# Flexi_encoder_BOB.net
KiCad netlist of a schematic drawn in Altium Designer
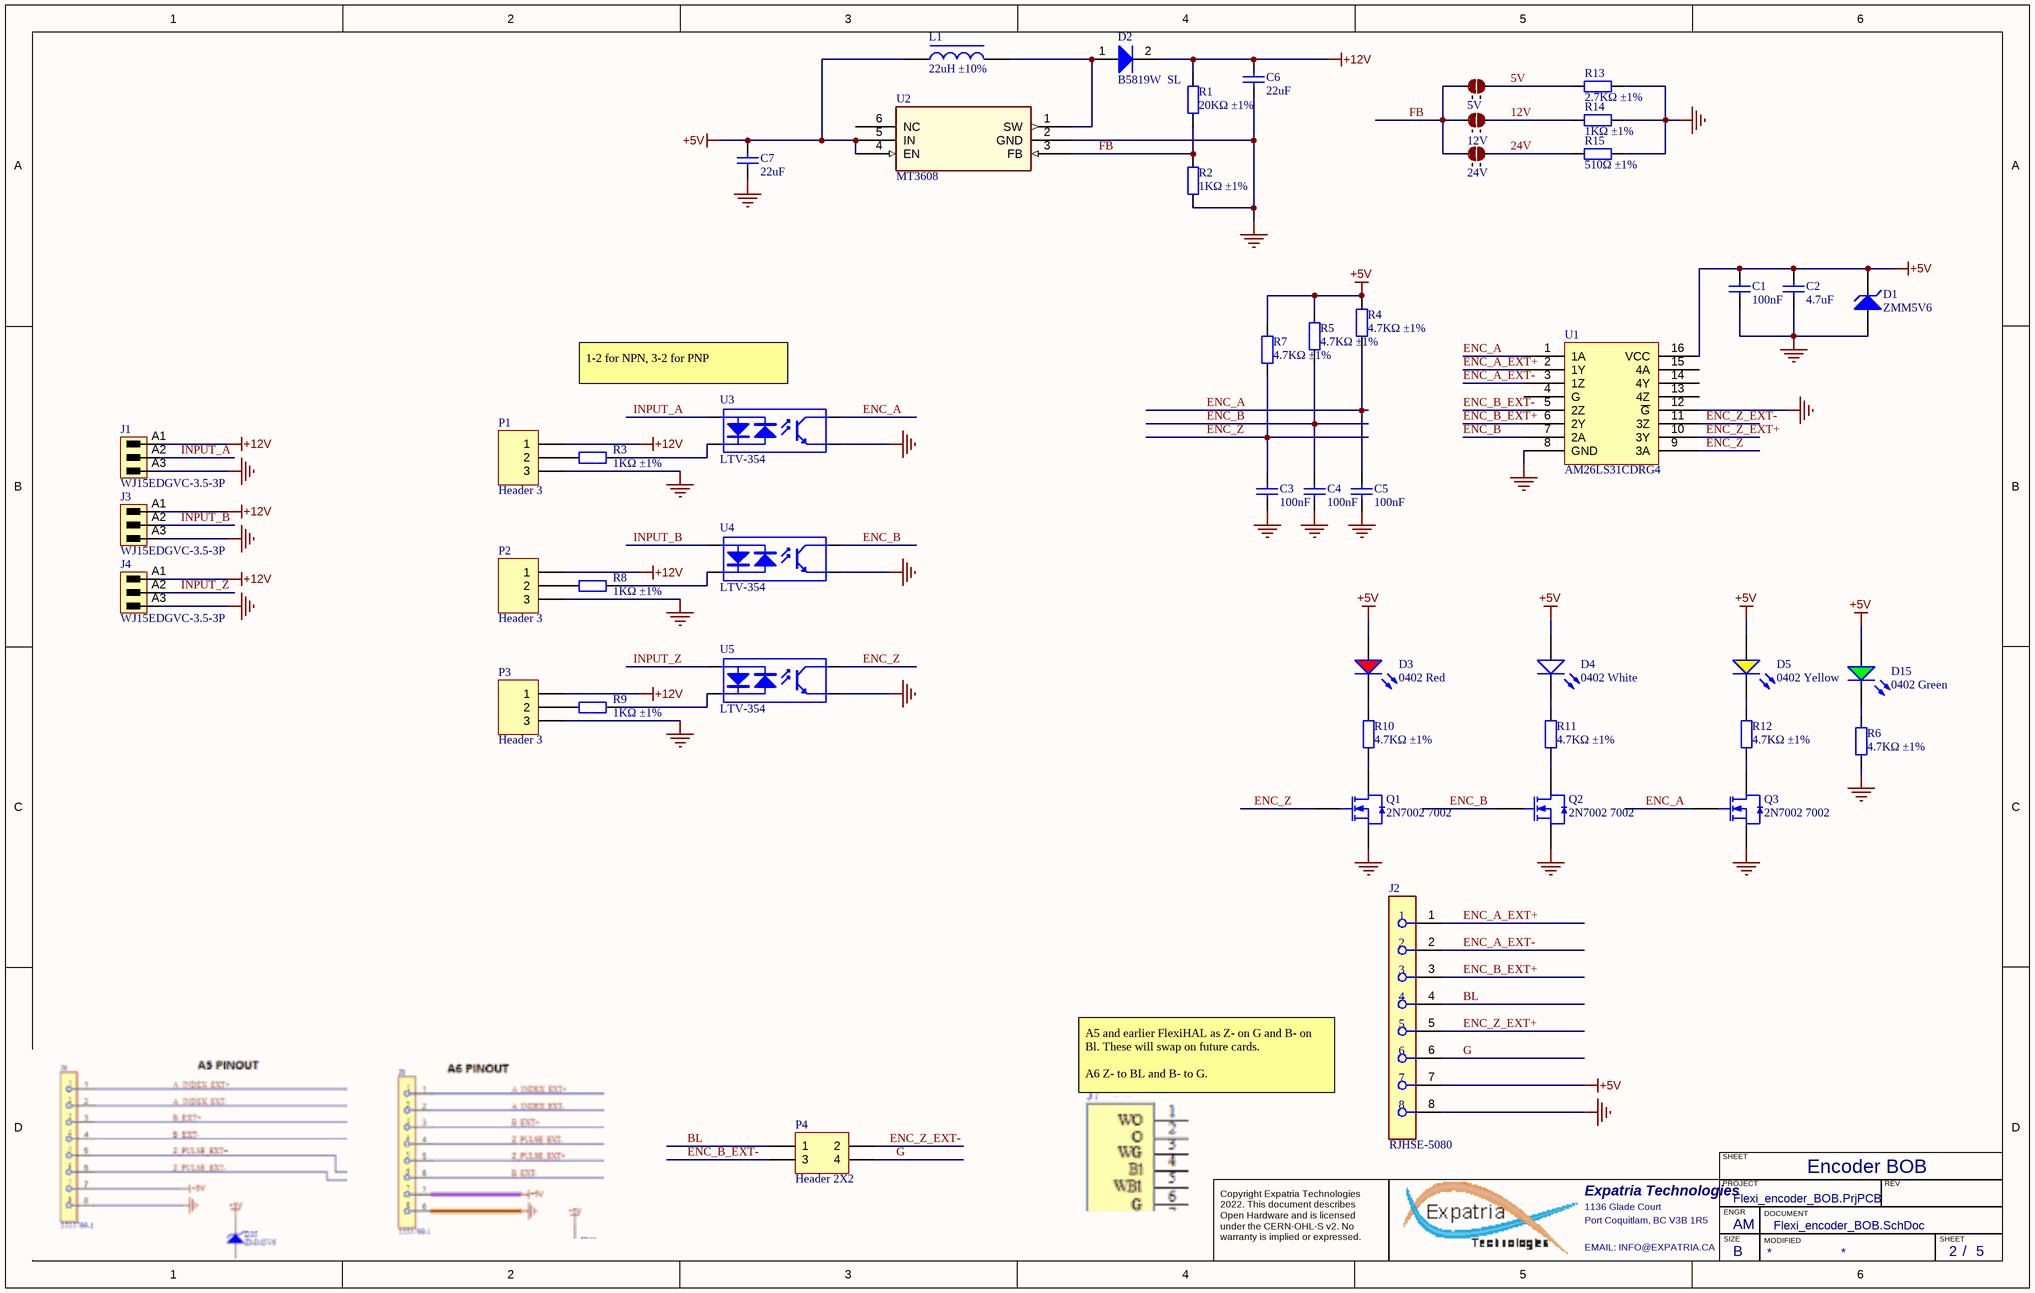
[diagram p0: Flexi_encoder_BOB.SchDoc]

(export (version "E")
  (design (tool "Eeschema 10.0.6"))
  (components
    (comp (ref "5V")
      (value "2 way net solder junction - Normally Open")
      (footprint "2waySolder_NO")
      (libsource (lib "NetTie") (part "2waySolderNO"))
    )
    (comp (ref "12V")
      (value "2 way net solder junction - Normally Open")
      (footprint "2waySolder_NO")
      (libsource (lib "NetTie") (part "2waySolderNO"))
    )
    (comp (ref "24V")
      (value "2 way net solder junction - Normally Open")
      (footprint "2waySolder_NO")
      (libsource (lib "NetTie") (part "2waySolderNO"))
    )
    (comp (ref "C1")
      (value "100nF")
      (footprint "0402_C")
      (description "Chip capacitors")
      (fields
        (field (name "MANUFACTURER") "Samsung Electro-Mechanics")
        (field (name "PARTNUMBER") "CL05B104KO5NNNC")
      )
      (libsource (lib "Cap") (part "0402 100nF (104) 10% 16V"))
    )
    (comp (ref "C2")
      (value "4.7uF")
      (footprint "0402_C")
      (description "Chip capacitor")
      (fields
        (field (name "MANUFACTURER") "Samsung Electro-Mechanics")
        (field (name "PARTNUMBER") "CL05A475MP5NRNC")
      )
      (libsource (lib "Cap") (part "0402 4.7uF (475) 20% 10V"))
    )
    (comp (ref "C3")
      (value "100nF")
      (footprint "0402_C")
      (description "Chip capacitors")
      (fields
        (field (name "MANUFACTURER") "Samsung Electro-Mechanics")
        (field (name "PARTNUMBER") "CL05B104KO5NNNC")
      )
      (libsource (lib "Cap") (part "0402 100nF (104) 10% 16V"))
    )
    (comp (ref "C4")
      (value "100nF")
      (footprint "0402_C")
      (description "Chip capacitors")
      (fields
        (field (name "MANUFACTURER") "Samsung Electro-Mechanics")
        (field (name "PARTNUMBER") "CL05B104KO5NNNC")
      )
      (libsource (lib "Cap") (part "0402 100nF (104) 10% 16V"))
    )
    (comp (ref "C5")
      (value "100nF")
      (footprint "0402_C")
      (description "Chip capacitors")
      (fields
        (field (name "MANUFACTURER") "Samsung Electro-Mechanics")
        (field (name "PARTNUMBER") "CL05B104KO5NNNC")
      )
      (libsource (lib "Cap") (part "0402 100nF (104) 10% 16V"))
    )
    (comp (ref "C6")
      (value "22uF")
      (footprint "0805_C")
      (description "Chip capacitors")
      (fields
        (field (name "MANUFACTURER") "Samsung Electro-Mechanics")
        (field (name "PARTNUMBER") "CL21A226MAQNNNE")
      )
      (libsource (lib "Cap") (part "0805 22uF (226) 20% 25V"))
    )
    (comp (ref "C7")
      (value "22uF")
      (footprint "0805_C")
      (description "Chip capacitors")
      (fields
        (field (name "MANUFACTURER") "Samsung Electro-Mechanics")
        (field (name "PARTNUMBER") "CL21A226MAQNNNE")
      )
      (libsource (lib "Cap") (part "0805 22uF (226) 20% 25V"))
    )
    (comp (ref "D1")
      (value "ZMM5V6")
      (footprint "LL-34")
      (description "500mW - 0.1uA @ 1V 5.6V LL-34 Zener Diodes ROHS")
      (libsource (lib "Zener") (part "LL-34 ZMM5V6"))
    )
    (comp (ref "D2")
      (value "B5819W  SL")
      (footprint "SOD-123")
      (description "Schottky Diode")
      (libsource (lib "Diode") (part "SOD-123 B5819W  SL"))
    )
    (comp (ref "D3")
      (value "0402 Red")
      (footprint "LED 0402_1005 RED")
      (description "LED")
      (libsource (lib "LED") (part "0402 LED Red"))
    )
    (comp (ref "D4")
      (value "0402 White")
      (footprint "LED 0402_1005 RED")
      (description "LED")
      (libsource (lib "LED") (part "0402 LED White"))
    )
    (comp (ref "D5")
      (value "0402 Yellow")
      (footprint "LED 0402_1005 RED")
      (description "LED")
      (libsource (lib "LED") (part "0402 LED Yellow"))
    )
    (comp (ref "D15")
      (value "0402 Green")
      (footprint "LED 0402_1005 RED")
      (description "LED")
      (libsource (lib "LED") (part "0402 LED Green"))
    )
    (comp (ref "J1")
      (value "WJ15EDGVC-3.5-3P")
      (footprint "691321100003 - 3.5mm  3p")
      (fields (field (name "MANUFACTURER") "Ningbo Kangnex Elec"))
      (libsource (lib "Universal_CNC_Breakout") (part "3.5mm Terminal Header 3p"))
    )
    (comp (ref "J2")
      (value "RJHSE-5080")
      (footprint "FP-RJHSE-5080-MFG")
      (description "CONN MOD JACK 8P8C R/A UNSHLD")
      (fields
        (field (name "MANUFACTURER PART NUMBER") "E5J88-00LJG2-L")
        (field (name "MANUFACTURER") "Pulse Electronics Network")
      )
      (libsource (lib "Altium Content Vault") (part "b0a0b555dd3abf3683e7c330df25cc4"))
    )
    (comp (ref "J3")
      (value "WJ15EDGVC-3.5-3P")
      (footprint "691321100003 - 3.5mm  3p")
      (fields (field (name "MANUFACTURER") "Ningbo Kangnex Elec"))
      (libsource (lib "Universal_CNC_Breakout") (part "3.5mm Terminal Header 3p"))
    )
    (comp (ref "J4")
      (value "WJ15EDGVC-3.5-3P")
      (footprint "691321100003 - 3.5mm  3p")
      (fields (field (name "MANUFACTURER") "Ningbo Kangnex Elec"))
      (libsource (lib "Universal_CNC_Breakout") (part "3.5mm Terminal Header 3p"))
    )
    (comp (ref "L1")
      (value "22uH ±10%")
      (footprint "INDP4040X30N")
      (description "1A 22uH ±20% SMD,4x4x3mm Power Inductors ROHS")
      (libsource (lib "IUD") (part "4x4x3 22uH 20%"))
    )
    (comp (ref "P1")
      (value "Header 3")
      (footprint "Miscellaneous Connectors:HDR1X3")
      (description "Header, 3-Pin")
      (fields (field (name "PUBLISHER") "Altium Limited"))
      (libsource (lib "Miscellaneous Connectors") (part "Header 3"))
    )
    (comp (ref "P2")
      (value "Header 3")
      (footprint "Miscellaneous Connectors:HDR1X3")
      (description "Header, 3-Pin")
      (fields (field (name "PUBLISHER") "Altium Limited"))
      (libsource (lib "Miscellaneous Connectors") (part "Header 3"))
    )
    (comp (ref "P3")
      (value "Header 3")
      (footprint "Miscellaneous Connectors:HDR1X3")
      (description "Header, 3-Pin")
      (fields (field (name "PUBLISHER") "Altium Limited"))
      (libsource (lib "Miscellaneous Connectors") (part "Header 3"))
    )
    (comp (ref "P4")
      (value "Header 2X2")
      (footprint "Miscellaneous Connectors:HDR2X2")
      (description "Header, 2-Pin, Dual row")
      (libsource (lib "Miscellaneous Connectors") (part "Header 2X2"))
    )
    (comp (ref "Q1")
      (value "2N7002 7002")
      (footprint "SOT-23(SOT-23-3)")
      (description "MOS(场效应管)")
      (libsource (lib "MOS") (part "2N7002 7002"))
    )
    (comp (ref "Q2")
      (value "2N7002 7002")
      (footprint "SOT-23(SOT-23-3)")
      (description "MOS(场效应管)")
      (libsource (lib "MOS") (part "2N7002 7002"))
    )
    (comp (ref "Q3")
      (value "2N7002 7002")
      (footprint "SOT-23(SOT-23-3)")
      (description "MOS(场效应管)")
      (libsource (lib "MOS") (part "2N7002 7002"))
    )
    (comp (ref "R1")
      (value "20KΩ ±1%")
      (footprint "0402_R")
      (description "Chip resistor")
      (fields (field (name "MANUFACTURER") "Uniroyal Elec") (field (name "PARTNUMBER") "0402WGF2002TCE"))
      (libsource (lib "RES") (part "0402 20K (2002) 1%"))
    )
    (comp (ref "R2")
      (value "1KΩ ±1%")
      (footprint "0402_R")
      (description "Chip resistor")
      (fields (field (name "MANUFACTURER") "Uniroyal Elec") (field (name "PARTNUMBER") "0402WGF1001TCE"))
      (libsource (lib "") (part "0402 1K (1001) 1%_1"))
    )
    (comp (ref "R3")
      (value "1KΩ ±1%")
      (footprint "0402_R")
      (description "Chip resistor")
      (fields (field (name "MANUFACTURER") "Uniroyal Elec") (field (name "PARTNUMBER") "0402WGF1001TCE"))
      (libsource (lib "RES") (part "0402 1K (1001) 1%"))
    )
    (comp (ref "R4")
      (value "4.7KΩ ±1%")
      (footprint "0402_R")
      (description "Chip resistor")
      (fields (field (name "MANUFACTURER") "Uniroyal Elec") (field (name "PARTNUMBER") "0402WGF4701TCE"))
      (libsource (lib "RES") (part "0402 4.7K (4701) 1%"))
    )
    (comp (ref "R5")
      (value "4.7KΩ ±1%")
      (footprint "0402_R")
      (description "Chip resistor")
      (fields (field (name "MANUFACTURER") "Uniroyal Elec") (field (name "PARTNUMBER") "0402WGF4701TCE"))
      (libsource (lib "RES") (part "0402 4.7K (4701) 1%"))
    )
    (comp (ref "R6")
      (value "4.7KΩ ±1%")
      (footprint "0402_R")
      (description "Chip resistor")
      (fields (field (name "MANUFACTURER") "Uniroyal Elec") (field (name "PARTNUMBER") "0402WGF4701TCE"))
      (libsource (lib "RES") (part "0402 4.7K (4701) 1%"))
    )
    (comp (ref "R7")
      (value "4.7KΩ ±1%")
      (footprint "0402_R")
      (description "Chip resistor")
      (fields (field (name "MANUFACTURER") "Uniroyal Elec") (field (name "PARTNUMBER") "0402WGF4701TCE"))
      (libsource (lib "RES") (part "0402 4.7K (4701) 1%"))
    )
    (comp (ref "R8")
      (value "1KΩ ±1%")
      (footprint "0402_R")
      (description "Chip resistor")
      (fields (field (name "MANUFACTURER") "Uniroyal Elec") (field (name "PARTNUMBER") "0402WGF1001TCE"))
      (libsource (lib "RES") (part "0402 1K (1001) 1%"))
    )
    (comp (ref "R9")
      (value "1KΩ ±1%")
      (footprint "0402_R")
      (description "Chip resistor")
      (fields (field (name "MANUFACTURER") "Uniroyal Elec") (field (name "PARTNUMBER") "0402WGF1001TCE"))
      (libsource (lib "RES") (part "0402 1K (1001) 1%"))
    )
    (comp (ref "R10")
      (value "4.7KΩ ±1%")
      (footprint "0402_R")
      (description "Chip resistor")
      (fields (field (name "MANUFACTURER") "Uniroyal Elec") (field (name "PARTNUMBER") "0402WGF4701TCE"))
      (libsource (lib "RES") (part "0402 4.7K (4701) 1%"))
    )
    (comp (ref "R11")
      (value "4.7KΩ ±1%")
      (footprint "0402_R")
      (description "Chip resistor")
      (fields (field (name "MANUFACTURER") "Uniroyal Elec") (field (name "PARTNUMBER") "0402WGF4701TCE"))
      (libsource (lib "RES") (part "0402 4.7K (4701) 1%"))
    )
    (comp (ref "R12")
      (value "4.7KΩ ±1%")
      (footprint "0402_R")
      (description "Chip resistor")
      (fields (field (name "MANUFACTURER") "Uniroyal Elec") (field (name "PARTNUMBER") "0402WGF4701TCE"))
      (libsource (lib "RES") (part "0402 4.7K (4701) 1%"))
    )
    (comp (ref "R13")
      (value "2.7KΩ ±1%")
      (footprint "0603_R")
      (description "Chip resistor")
      (fields (field (name "MANUFACTURER") "Uniroyal Elec") (field (name "PARTNUMBER") "0603WAF2701T5E"))
      (libsource (lib "RES") (part "0603 2.7K (2701) 1%"))
    )
    (comp (ref "R14")
      (value "1KΩ ±1%")
      (footprint "0402_R")
      (description "Chip resistor")
      (fields (field (name "MANUFACTURER") "Uniroyal Elec") (field (name "PARTNUMBER") "0402WGF1001TCE"))
      (libsource (lib "RES") (part "0402 1K (1001) 1%"))
    )
    (comp (ref "R15")
      (value "510Ω ±1%")
      (footprint "0402_R")
      (description "Chip resistor")
      (fields (field (name "MANUFACTURER") "Uniroyal Elec") (field (name "PARTNUMBER") "0402WGF5100TCE"))
      (libsource (lib "RES") (part "0402 510R (5100) 1%"))
    )
    (comp (ref "U1")
      (value "AM26LS31CDRG4")
      (footprint "SOIC-16_150mil")
      (description "4/0 Driver - RS422, RS485 16-SOIC")
      (libsource (lib "IC") (part "AM26LS31CDRG4_[C6179]"))
    )
    (comp (ref "U2")
      (value "MT3608")
      (footprint "TSOT23-6SOT23-6_AER")
      (description "No Description Available")
      (libsource (lib "Universal_CNC_Breakout") (part "MT3608"))
    )
    (comp (ref "U3")
      (value "LTV-354")
      (footprint "Miscellaneous Devices LC:SOP-4_P2.54")
      (libsource (lib "IC") (part "LTV-354"))
    )
    (comp (ref "U4")
      (value "LTV-354")
      (footprint "Miscellaneous Devices LC:SOP-4_P2.54")
      (libsource (lib "IC") (part "LTV-354"))
    )
    (comp (ref "U5")
      (value "LTV-354")
      (footprint "Miscellaneous Devices LC:SOP-4_P2.54")
      (libsource (lib "IC") (part "LTV-354"))
    )
  )
  (nets
    (net (code "1") (name "+5V") (class "Default")
      (node (ref "C1") (pin "1") (pinfunction "1_1") (pintype "passive"))
      (node (ref "C2") (pin "1") (pinfunction "1_1") (pintype "passive"))
      (node (ref "C7") (pin "2") (pinfunction "2_2") (pintype "passive"))
      (node (ref "D1") (pin "2") (pinfunction "K_2") (pintype "passive"))
      (node (ref "D15") (pin "A") (pinfunction "A_A") (pintype "passive"))
      (node (ref "D3") (pin "A") (pinfunction "A_A") (pintype "passive"))
      (node (ref "D4") (pin "A") (pinfunction "A_A") (pintype "passive"))
      (node (ref "D5") (pin "A") (pinfunction "A_A") (pintype "passive"))
      (node (ref "J2") (pin "7") (pinfunction "7_7") (pintype "passive"))
      (node (ref "L1") (pin "1") (pinfunction "1_1") (pintype "passive"))
      (node (ref "R4") (pin "2") (pinfunction "2_2") (pintype "passive"))
      (node (ref "R5") (pin "2") (pinfunction "2_2") (pintype "passive"))
      (node (ref "R7") (pin "2") (pinfunction "2_2") (pintype "passive"))
      (node (ref "U1") (pin "16") (pinfunction "VCC_16") (pintype "passive"))
      (node (ref "U2") (pin "4") (pinfunction "EN_4") (pintype "input"))
      (node (ref "U2") (pin "5") (pinfunction "IN_5") (pintype "power_in"))
    )
    (net (code "2") (name "+12V") (class "Default")
      (node (ref "C6") (pin "2") (pinfunction "2_2") (pintype "passive"))
      (node (ref "D2") (pin "2") (pinfunction "K_2") (pintype "passive"))
      (node (ref "J1") (pin "A1") (pinfunction "A1_A1") (pintype "passive"))
      (node (ref "J3") (pin "A1") (pinfunction "A1_A1") (pintype "passive"))
      (node (ref "J4") (pin "A1") (pinfunction "A1_A1") (pintype "passive"))
      (node (ref "P1") (pin "1") (pinfunction "1_1") (pintype "passive"))
      (node (ref "P2") (pin "1") (pinfunction "1_1") (pintype "passive"))
      (node (ref "P3") (pin "1") (pinfunction "1_1") (pintype "passive"))
      (node (ref "R1") (pin "2") (pinfunction "2_2") (pintype "passive"))
    )
    (net (code "3") (name "/5V") (class "Default")
      (node (ref "5V") (pin "2") (pinfunction "2_2") (pintype "passive"))
      (node (ref "R13") (pin "1") (pinfunction "1_1") (pintype "passive"))
    )
    (net (code "4") (name "/12V") (class "Default")
      (node (ref "12V") (pin "2") (pinfunction "2_2") (pintype "passive"))
      (node (ref "R14") (pin "2") (pinfunction "2_2") (pintype "passive"))
    )
    (net (code "5") (name "/24V") (class "Default")
      (node (ref "24V") (pin "2") (pinfunction "2_2") (pintype "passive"))
      (node (ref "R15") (pin "1") (pinfunction "1_1") (pintype "passive"))
    )
    (net (code "6") (name "/BL") (class "Default")
      (node (ref "J2") (pin "4") (pinfunction "4_4") (pintype "passive"))
      (node (ref "P4") (pin "1") (pinfunction "1_1") (pintype "passive"))
    )
    (net (code "7") (name "/ENC_A") (class "Default")
      (node (ref "C5") (pin "1") (pinfunction "1_1") (pintype "passive"))
      (node (ref "Q3") (pin "1") (pinfunction "G_1") (pintype "passive"))
      (node (ref "R4") (pin "1") (pinfunction "1_1") (pintype "passive"))
      (node (ref "U1") (pin "1") (pinfunction "1A_1") (pintype "passive"))
      (node (ref "U3") (pin "4") (pinfunction "C_4") (pintype "passive"))
    )
    (net (code "8") (name "/ENC_A_EXT+") (class "Default")
      (node (ref "J2") (pin "1") (pinfunction "1_1") (pintype "passive"))
      (node (ref "U1") (pin "2") (pinfunction "1Y_2") (pintype "passive"))
    )
    (net (code "9") (name "/ENC_A_EXT-") (class "Default")
      (node (ref "J2") (pin "2") (pinfunction "2_2") (pintype "passive"))
      (node (ref "U1") (pin "3") (pinfunction "1Z_3") (pintype "passive"))
    )
    (net (code "10") (name "/ENC_B") (class "Default")
      (node (ref "C4") (pin "1") (pinfunction "1_1") (pintype "passive"))
      (node (ref "Q2") (pin "1") (pinfunction "G_1") (pintype "passive"))
      (node (ref "R5") (pin "1") (pinfunction "1_1") (pintype "passive"))
      (node (ref "U1") (pin "7") (pinfunction "2A_7") (pintype "passive"))
      (node (ref "U4") (pin "4") (pinfunction "C_4") (pintype "passive"))
    )
    (net (code "11") (name "/ENC_B_EXT+") (class "Default")
      (node (ref "J2") (pin "3") (pinfunction "3_3") (pintype "passive"))
      (node (ref "U1") (pin "6") (pinfunction "2Y_6") (pintype "passive"))
    )
    (net (code "12") (name "/ENC_B_EXT-") (class "Default")
      (node (ref "P4") (pin "3") (pinfunction "3_3") (pintype "passive"))
      (node (ref "U1") (pin "5") (pinfunction "2Z_5") (pintype "passive"))
    )
    (net (code "13") (name "/ENC_Z") (class "Default")
      (node (ref "C3") (pin "1") (pinfunction "1_1") (pintype "passive"))
      (node (ref "Q1") (pin "1") (pinfunction "G_1") (pintype "passive"))
      (node (ref "R7") (pin "1") (pinfunction "1_1") (pintype "passive"))
      (node (ref "U1") (pin "9") (pinfunction "3A_9") (pintype "passive"))
      (node (ref "U5") (pin "4") (pinfunction "C_4") (pintype "passive"))
    )
    (net (code "14") (name "/ENC_Z_EXT+") (class "Default")
      (node (ref "J2") (pin "5") (pinfunction "5_5") (pintype "passive"))
      (node (ref "U1") (pin "10") (pinfunction "3Y_10") (pintype "passive"))
    )
    (net (code "15") (name "/ENC_Z_EXT-") (class "Default")
      (node (ref "P4") (pin "2") (pinfunction "2_2") (pintype "passive"))
      (node (ref "U1") (pin "11") (pinfunction "3Z_11") (pintype "passive"))
    )
    (net (code "16") (name "/FB") (class "Default")
      (node (ref "12V") (pin "1") (pinfunction "1_1") (pintype "passive"))
      (node (ref "24V") (pin "1") (pinfunction "1_1") (pintype "passive"))
      (node (ref "5V") (pin "1") (pinfunction "1_1") (pintype "passive"))
      (node (ref "R1") (pin "1") (pinfunction "1_1") (pintype "passive"))
      (node (ref "R2") (pin "2") (pinfunction "2_2") (pintype "passive"))
      (node (ref "U2") (pin "3") (pinfunction "FB_3") (pintype "input"))
    )
    (net (code "17") (name "/G") (class "Default")
      (node (ref "J2") (pin "6") (pinfunction "6_6") (pintype "passive"))
      (node (ref "P4") (pin "4") (pinfunction "4_4") (pintype "passive"))
    )
    (net (code "18") (name "/INPUT_A") (class "Default")
      (node (ref "J1") (pin "A2") (pinfunction "A2_A2") (pintype "passive"))
      (node (ref "U3") (pin "1") (pinfunction "A_1") (pintype "passive"))
    )
    (net (code "19") (name "/INPUT_B") (class "Default")
      (node (ref "J3") (pin "A2") (pinfunction "A2_A2") (pintype "passive"))
      (node (ref "U4") (pin "1") (pinfunction "A_1") (pintype "passive"))
    )
    (net (code "20") (name "/INPUT_Z") (class "Default")
      (node (ref "J4") (pin "A2") (pinfunction "A2_A2") (pintype "passive"))
      (node (ref "U5") (pin "1") (pinfunction "A_1") (pintype "passive"))
    )
    (net (code "21") (name "GND") (class "Default")
      (node (ref "C1") (pin "2") (pinfunction "2_2") (pintype "passive"))
      (node (ref "C2") (pin "2") (pinfunction "2_2") (pintype "passive"))
      (node (ref "C3") (pin "2") (pinfunction "2_2") (pintype "passive"))
      (node (ref "C4") (pin "2") (pinfunction "2_2") (pintype "passive"))
      (node (ref "C5") (pin "2") (pinfunction "2_2") (pintype "passive"))
      (node (ref "C6") (pin "1") (pinfunction "1_1") (pintype "passive"))
      (node (ref "C7") (pin "1") (pinfunction "1_1") (pintype "passive"))
      (node (ref "D1") (pin "1") (pinfunction "A_1") (pintype "passive"))
      (node (ref "J1") (pin "A3") (pinfunction "A3_A3") (pintype "passive"))
      (node (ref "J2") (pin "8") (pinfunction "8_8") (pintype "passive"))
      (node (ref "J3") (pin "A3") (pinfunction "A3_A3") (pintype "passive"))
      (node (ref "J4") (pin "A3") (pinfunction "A3_A3") (pintype "passive"))
      (node (ref "P1") (pin "3") (pinfunction "3_3") (pintype "passive"))
      (node (ref "P2") (pin "3") (pinfunction "3_3") (pintype "passive"))
      (node (ref "P3") (pin "3") (pinfunction "3_3") (pintype "passive"))
      (node (ref "Q1") (pin "2") (pinfunction "S_2") (pintype "passive"))
      (node (ref "Q2") (pin "2") (pinfunction "S_2") (pintype "passive"))
      (node (ref "Q3") (pin "2") (pinfunction "S_2") (pintype "passive"))
      (node (ref "R13") (pin "2") (pinfunction "2_2") (pintype "passive"))
      (node (ref "R14") (pin "1") (pinfunction "1_1") (pintype "passive"))
      (node (ref "R15") (pin "2") (pinfunction "2_2") (pintype "passive"))
      (node (ref "R2") (pin "1") (pinfunction "1_1") (pintype "passive"))
      (node (ref "R6") (pin "1") (pinfunction "1_1") (pintype "passive"))
      (node (ref "U1") (pin "12") (pinfunction "~{G}_12") (pintype "passive"))
      (node (ref "U1") (pin "8") (pinfunction "GND_8") (pintype "passive"))
      (node (ref "U2") (pin "2") (pinfunction "GND_2") (pintype "power_in"))
      (node (ref "U3") (pin "3") (pinfunction "E_3") (pintype "passive"))
      (node (ref "U4") (pin "3") (pinfunction "E_3") (pintype "passive"))
      (node (ref "U5") (pin "3") (pinfunction "E_3") (pintype "passive"))
    )
    (net (code "22") (name "Net-(D2-A)") (class "Default")
      (node (ref "D2") (pin "1") (pinfunction "A_1") (pintype "passive"))
      (node (ref "L1") (pin "2") (pinfunction "2_2") (pintype "passive"))
      (node (ref "U2") (pin "1") (pinfunction "SW_1") (pintype "output"))
    )
    (net (code "23") (name "Net-(D3-PadK)") (class "Default")
      (node (ref "D3") (pin "K") (pinfunction "K_K") (pintype "passive"))
      (node (ref "R10") (pin "2") (pinfunction "2_2") (pintype "passive"))
    )
    (net (code "24") (name "Net-(D4-PadK)") (class "Default")
      (node (ref "D4") (pin "K") (pinfunction "K_K") (pintype "passive"))
      (node (ref "R11") (pin "2") (pinfunction "2_2") (pintype "passive"))
    )
    (net (code "25") (name "Net-(D5-PadK)") (class "Default")
      (node (ref "D5") (pin "K") (pinfunction "K_K") (pintype "passive"))
      (node (ref "R12") (pin "2") (pinfunction "2_2") (pintype "passive"))
    )
    (net (code "26") (name "Net-(D15-PadK)") (class "Default")
      (node (ref "D15") (pin "K") (pinfunction "K_K") (pintype "passive"))
      (node (ref "R6") (pin "2") (pinfunction "2_2") (pintype "passive"))
    )
    (net (code "27") (name "Net-(P1-Pad2)") (class "Default")
      (node (ref "P1") (pin "2") (pinfunction "2_2") (pintype "passive"))
      (node (ref "R3") (pin "2") (pinfunction "2_2") (pintype "passive"))
    )
    (net (code "28") (name "Net-(P2-Pad2)") (class "Default")
      (node (ref "P2") (pin "2") (pinfunction "2_2") (pintype "passive"))
      (node (ref "R8") (pin "2") (pinfunction "2_2") (pintype "passive"))
    )
    (net (code "29") (name "Net-(P3-Pad2)") (class "Default")
      (node (ref "P3") (pin "2") (pinfunction "2_2") (pintype "passive"))
      (node (ref "R9") (pin "2") (pinfunction "2_2") (pintype "passive"))
    )
    (net (code "30") (name "Net-(Q1-D)") (class "Default")
      (node (ref "Q1") (pin "3") (pinfunction "D_3") (pintype "passive"))
      (node (ref "R10") (pin "1") (pinfunction "1_1") (pintype "passive"))
    )
    (net (code "31") (name "Net-(Q2-D)") (class "Default")
      (node (ref "Q2") (pin "3") (pinfunction "D_3") (pintype "passive"))
      (node (ref "R11") (pin "1") (pinfunction "1_1") (pintype "passive"))
    )
    (net (code "32") (name "Net-(Q3-D)") (class "Default")
      (node (ref "Q3") (pin "3") (pinfunction "D_3") (pintype "passive"))
      (node (ref "R12") (pin "1") (pinfunction "1_1") (pintype "passive"))
    )
    (net (code "33") (name "Net-(U3-K)") (class "Default")
      (node (ref "R3") (pin "1") (pinfunction "1_1") (pintype "passive"))
      (node (ref "U3") (pin "2") (pinfunction "K_2") (pintype "passive"))
    )
    (net (code "34") (name "Net-(U4-K)") (class "Default")
      (node (ref "R8") (pin "1") (pinfunction "1_1") (pintype "passive"))
      (node (ref "U4") (pin "2") (pinfunction "K_2") (pintype "passive"))
    )
    (net (code "35") (name "Net-(U5-K)") (class "Default")
      (node (ref "R9") (pin "1") (pinfunction "1_1") (pintype "passive"))
      (node (ref "U5") (pin "2") (pinfunction "K_2") (pintype "passive"))
    )
    (net (code "36") (name "unconnected-(U1-4A-Pad15)") (class "Default")
      (node (ref "U1") (pin "15") (pinfunction "4A_15") (pintype "passive"))
    )
    (net (code "37") (name "unconnected-(U1-4Y-Pad14)") (class "Default")
      (node (ref "U1") (pin "14") (pinfunction "4Y_14") (pintype "passive"))
    )
    (net (code "38") (name "unconnected-(U1-4Z-Pad13)") (class "Default")
      (node (ref "U1") (pin "13") (pinfunction "4Z_13") (pintype "passive"))
    )
    (net (code "39") (name "unconnected-(U1-G-Pad4)") (class "Default")
      (node (ref "U1") (pin "4") (pinfunction "G_4") (pintype "passive"))
    )
    (net (code "40") (name "unconnected-(U2-NC-Pad6)") (class "Default")
      (node (ref "U2") (pin "6") (pinfunction "NC_6") (pintype "passive"))
    )
  )
)
